# 100_ESP.net
KiCad netlist of a schematic drawn in Altium Designer
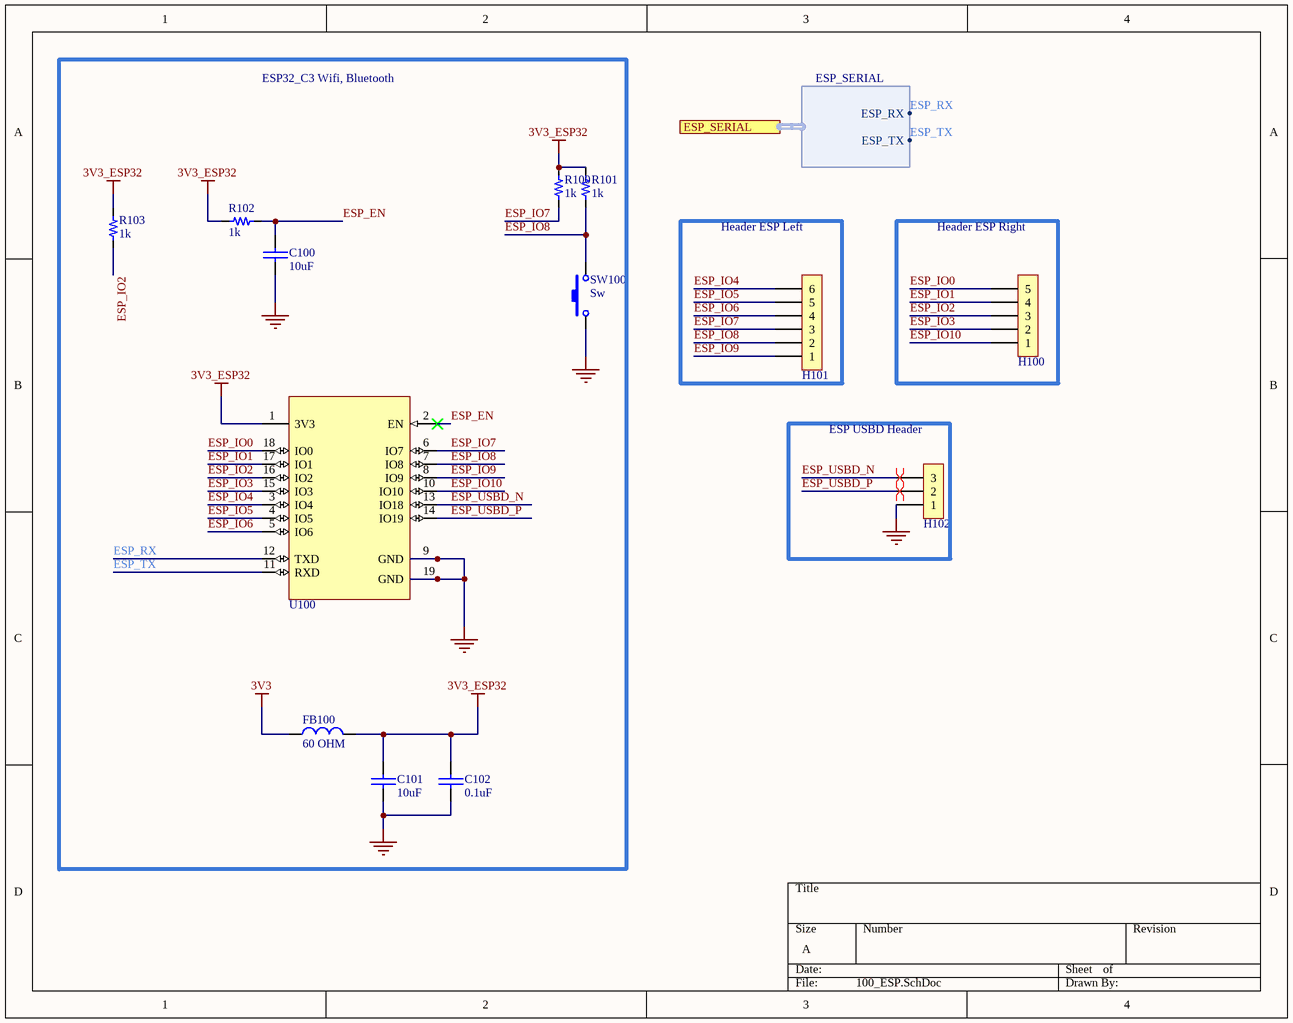
[diagram p0: 100_ESP.SchDoc]

(export (version "E")
  (design (tool "Eeschema 10.0.6"))
  (components
    (comp (ref "C100")
      (value "10uF")
      (footprint "0805_cap")
      (description "25V 10uF X5R ±10% 0805 Multilayer Ceramic Capacitors MLCC - SMD/SMT ROHS")
      (fields
        (field (name "MANUFACTURER") "Samsung Electro-Mechanics")
        (field (name "MANUFACTURER PART NUMBER") "CL21A106KAYNNNE")
      )
      (libsource (lib "shared_lib") (part "Cap_10uF_0805_25V_"))
    )
    (comp (ref "C101")
      (value "10uF")
      (footprint "0805_cap")
      (description "25V 10uF X5R ±10% 0805 Multilayer Ceramic Capacitors MLCC - SMD/SMT ROHS")
      (fields
        (field (name "MANUFACTURER") "Samsung Electro-Mechanics")
        (field (name "MANUFACTURER PART NUMBER") "CL21A106KAYNNNE")
      )
      (libsource (lib "shared_lib") (part "Cap_10uF_0805_25V_"))
    )
    (comp (ref "C102")
      (value "0.1uF")
      (footprint "0603_cap")
      (description "50V 100nF Y5V -20%~+80% 0603 Multilayer Ceramic Capacitors MLCC - SMD/SMT ROHS")
      (fields
        (field (name "MANUFACTURER") "Walsin Tech Corp")
        (field (name "MANUFACTURER PART NUMBER") "0603F104Z500CT")
      )
      (libsource (lib "shared_lib") (part "Cap_0.1uF_0603_50V"))
    )
    (comp (ref "FB100")
      (value "60 OHM")
      (footprint "0603_fb")
      (description "2A 1 100mΩ 60Ω@100MHz ±25% 0603 Ferrite Beads ROHS")
      (fields
        (field (name "MANUFACTURER") "TAI-TECH")
        (field (name "MANUFACTURER PART NUMBER") "HCB1608KF-600T20")
      )
      (libsource (lib "shared_lib") (part "FB_60_0603_2A"))
    )
    (comp (ref "H100")
      (value "5x1")
      (footprint "H_5x1_TH_100mil")
      (description "H_Male_5x1_TH_100mil")
      (libsource (lib "shared_lib") (part "H_Male_5x1_TH_100mil"))
    )
    (comp (ref "H101")
      (value "6x1")
      (footprint "H_6x1_TH_100mil")
      (description "H_Male_6x1_TH_100mil")
      (libsource (lib "shared_lib") (part "H_Male_6x1_TH_100mil"))
    )
    (comp (ref "H102")
      (value "3x1")
      (footprint "H_3X1_TH_100mil")
      (description "H_Male_3x1_TH_100mil")
      (libsource (lib "shared_lib") (part "H_Male_3x1_TH_100mil"))
    )
    (comp (ref "R100")
      (value "1k")
      (footprint "0603_res")
      (description "RES SMD 1k OHM 5% 1/10W 0603")
      (fields
        (field (name "MANUFACTURER") "FOJAN")
        (field (name "MANUFACTURER PART NUMBER") "FRC0603J102 TS")
      )
      (libsource (lib "shared_lib") (part "Res_1k_0603_1/10W"))
    )
    (comp (ref "R101")
      (value "1k")
      (footprint "0603_res")
      (description "RES SMD 1k OHM 5% 1/10W 0603")
      (fields
        (field (name "MANUFACTURER") "FOJAN")
        (field (name "MANUFACTURER PART NUMBER") "FRC0603J102 TS")
      )
      (libsource (lib "shared_lib") (part "Res_1k_0603_1/10W"))
    )
    (comp (ref "R102")
      (value "1k")
      (footprint "0603_res")
      (description "RES SMD 1k OHM 5% 1/10W 0603")
      (fields
        (field (name "MANUFACTURER") "FOJAN")
        (field (name "MANUFACTURER PART NUMBER") "FRC0603J102 TS")
      )
      (libsource (lib "shared_lib") (part "Res_1k_0603_1/10W"))
    )
    (comp (ref "R103")
      (value "1k")
      (footprint "0603_res")
      (description "RES SMD 1k OHM 5% 1/10W 0603")
      (fields
        (field (name "MANUFACTURER") "FOJAN")
        (field (name "MANUFACTURER PART NUMBER") "FRC0603J102 TS")
      )
      (libsource (lib "shared_lib") (part "Res_1k_0603_1/10W"))
    )
    (comp (ref "SW100")
      (value "Sw")
      (footprint "Sw_PUSH_4.5x4.5x5mm")
      (description "SWITCH TACTILE SPST-NO 0.05A 12V")
      (fields
        (field (name "MANUFACTURER") "BZCN")
        (field (name "MANUFACTURER PART NUMBER") "TSC015A05026A")
        (field (name "LAST MODIFIED BY") "N-A.Potosi")
      )
      (libsource (lib "shared_lib") (part "Sw_PUSH_4.5x4.5x5.0xmm"))
    )
    (comp (ref "U100")
      (value "ESP32-C3-WROOM-02-N4")
      (footprint "ESP32-C3-WROOM-02-N4")
      (description "RF TXRX MOD BT WIFI PCB TH SMD")
      (fields (field (name "MANUFACTURER") "Espressif Systems"))
      (libsource (lib "shared_lib") (part "MCU_ESP32-C3-WROOM-02-N4"))
    )
  )
  (nets
    (net (code "2") (name "/ESP_EN") (class "Default")
      (node (ref "C100") (pin "1") (pinfunction "1_1") (pintype "passive"))
      (node (ref "R102") (pin "1") (pinfunction "1_1") (pintype "passive"))
      (node (ref "U100") (pin "2") (pinfunction "EN_2") (pintype "input"))
    )
    (net (code "3") (name "/ESP_IO0") (class "Default")
      (node (ref "H100") (pin "5") (pinfunction "5_5") (pintype "passive"))
      (node (ref "U100") (pin "18") (pinfunction "IO0_18") (pintype "bidirectional"))
    )
    (net (code "4") (name "/ESP_IO1") (class "Default")
      (node (ref "H100") (pin "4") (pinfunction "4_4") (pintype "passive"))
      (node (ref "U100") (pin "17") (pinfunction "IO1_17") (pintype "bidirectional"))
    )
    (net (code "5") (name "/ESP_IO2") (class "Default")
      (node (ref "H100") (pin "3") (pinfunction "3_3") (pintype "passive"))
      (node (ref "R103") (pin "1") (pinfunction "1_1") (pintype "passive"))
      (node (ref "U100") (pin "16") (pinfunction "IO2_16") (pintype "bidirectional"))
    )
    (net (code "6") (name "/ESP_IO3") (class "Default")
      (node (ref "H100") (pin "2") (pinfunction "2_2") (pintype "passive"))
      (node (ref "U100") (pin "15") (pinfunction "IO3_15") (pintype "bidirectional"))
    )
    (net (code "7") (name "/ESP_IO4") (class "Default")
      (node (ref "H101") (pin "6") (pinfunction "6_6") (pintype "passive"))
      (node (ref "U100") (pin "3") (pinfunction "IO4_3") (pintype "bidirectional"))
    )
    (net (code "8") (name "/ESP_IO5") (class "Default")
      (node (ref "H101") (pin "5") (pinfunction "5_5") (pintype "passive"))
      (node (ref "U100") (pin "4") (pinfunction "IO5_4") (pintype "bidirectional"))
    )
    (net (code "9") (name "/ESP_IO6") (class "Default")
      (node (ref "H101") (pin "4") (pinfunction "4_4") (pintype "passive"))
      (node (ref "U100") (pin "5") (pinfunction "IO6_5") (pintype "bidirectional"))
    )
    (net (code "10") (name "/ESP_IO7") (class "Default")
      (node (ref "H101") (pin "3") (pinfunction "3_3") (pintype "passive"))
      (node (ref "R100") (pin "1") (pinfunction "1_1") (pintype "passive"))
      (node (ref "U100") (pin "6") (pinfunction "IO7_6") (pintype "bidirectional"))
    )
    (net (code "11") (name "/ESP_IO8") (class "Default")
      (node (ref "H101") (pin "2") (pinfunction "2_2") (pintype "passive"))
      (node (ref "R101") (pin "1") (pinfunction "1_1") (pintype "passive"))
      (node (ref "SW100") (pin "2") (pinfunction "2_2") (pintype "passive"))
      (node (ref "U100") (pin "7") (pinfunction "IO8_7") (pintype "bidirectional"))
    )
    (net (code "12") (name "/ESP_IO9") (class "Default")
      (node (ref "H101") (pin "1") (pinfunction "1_1") (pintype "passive"))
      (node (ref "U100") (pin "8") (pinfunction "IO9_8") (pintype "bidirectional"))
    )
    (net (code "13") (name "/ESP_IO10") (class "Default")
      (node (ref "H100") (pin "1") (pinfunction "1_1") (pintype "passive"))
      (node (ref "U100") (pin "10") (pinfunction "IO10_10") (pintype "bidirectional"))
    )
    (net (code "14") (name "/ESP_RX") (class "Default")
      (node (ref "U100") (pin "12") (pinfunction "TXD_12") (pintype "bidirectional"))
    )
    (net (code "15") (name "/ESP_TX") (class "Default")
      (node (ref "U100") (pin "11") (pinfunction "RXD_11") (pintype "bidirectional"))
    )
    (net (code "16") (name "/ESP_USBD_N") (class "Default")
      (node (ref "H102") (pin "3") (pinfunction "3_3") (pintype "passive"))
      (node (ref "U100") (pin "13") (pinfunction "IO18_13") (pintype "bidirectional"))
    )
    (net (code "17") (name "/ESP_USBD_P") (class "Default")
      (node (ref "H102") (pin "2") (pinfunction "2_2") (pintype "passive"))
      (node (ref "U100") (pin "14") (pinfunction "IO19_14") (pintype "bidirectional"))
    )
    (net (code "19") (name "3V3") (class "Default")
      (node (ref "FB100") (pin "1") (pinfunction "1_1") (pintype "passive"))
    )
    (net (code "20") (name "3V3_ESP32") (class "Default")
      (node (ref "C101") (pin "1") (pinfunction "1_1") (pintype "passive"))
      (node (ref "C102") (pin "1") (pinfunction "1_1") (pintype "passive"))
      (node (ref "FB100") (pin "2") (pinfunction "2_2") (pintype "passive"))
      (node (ref "R100") (pin "2") (pinfunction "2_2") (pintype "passive"))
      (node (ref "R101") (pin "2") (pinfunction "2_2") (pintype "passive"))
      (node (ref "R102") (pin "2") (pinfunction "2_2") (pintype "passive"))
      (node (ref "R103") (pin "2") (pinfunction "2_2") (pintype "passive"))
      (node (ref "U100") (pin "1") (pinfunction "3V3_1") (pintype "power_in"))
    )
    (net (code "21") (name "GND") (class "Default")
      (node (ref "C100") (pin "2") (pinfunction "2_2") (pintype "passive"))
      (node (ref "C101") (pin "2") (pinfunction "2_2") (pintype "passive"))
      (node (ref "C102") (pin "2") (pinfunction "2_2") (pintype "passive"))
      (node (ref "H102") (pin "1") (pinfunction "1_1") (pintype "passive"))
      (node (ref "SW100") (pin "1") (pinfunction "1_1") (pintype "passive"))
      (node (ref "U100") (pin "19") (pinfunction "GND_19") (pintype "power_in"))
      (node (ref "U100") (pin "9") (pinfunction "GND_9") (pintype "power_in"))
    )
  )
)
